# TUDSSL_condenar__Hardware_PCBs_Mainboard.net
KiCad netlist of a schematic drawn in Altium Designer
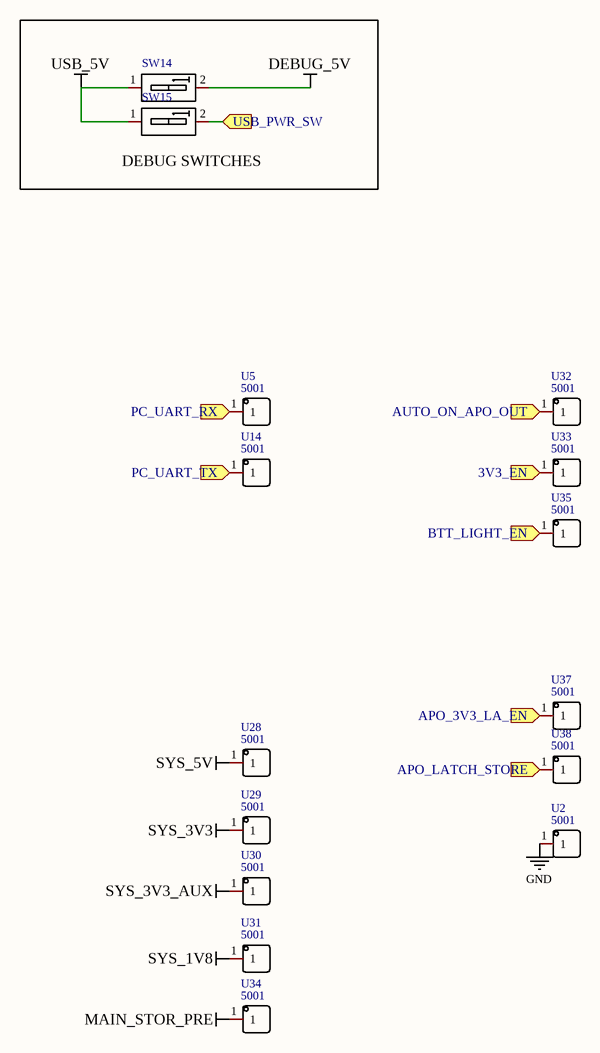
[diagram p0: TUDSSL_condenar__Hardware_PCBs_Mainboard_Board_TUD-V2-EnergyHarvestingConsole_TUD-EnergyHarvestingConsole_1__4_Debugging.schdoc]

(export (version "E")
  (design (tool "Eeschema 10.0.6"))
  (components
    (comp (ref "SW14")
      (value "DSIC01LSGET")
      (description "Type:平拨，凸起式 Circuit:SPST Number of Positions:1 Lead Pitch:2.54mm Color:Black")
      (fields (field (name "MANUFACTURER") "YE"))
      (libsource (lib "altium-import") (part "root_0_DSIC01LSGET_"))
    )
    (comp (ref "SW15")
      (value "DSIC01LSGET")
      (description "Type:平拨，凸起式 Circuit:SPST Number of Positions:1 Lead Pitch:2.54mm Color:Black")
      (fields (field (name "MANUFACTURER") "YE"))
      (libsource (lib "altium-import") (part "root_0_DSIC01LSGET_"))
    )
    (comp (ref "U2")
      (value "5001")
      (fields (field (name "NAME") "5001") (field (name "MANUFACTURER") "Keystone"))
      (libsource (lib "altium-import") (part "root_0_5001_"))
    )
    (comp (ref "U5")
      (value "5001")
      (fields (field (name "NAME") "5001") (field (name "MANUFACTURER") "Keystone"))
      (libsource (lib "altium-import") (part "root_0_5001_"))
    )
    (comp (ref "U14")
      (value "5001")
      (fields (field (name "NAME") "5001") (field (name "MANUFACTURER") "Keystone"))
      (libsource (lib "altium-import") (part "root_0_5001_"))
    )
    (comp (ref "U28")
      (value "5001")
      (fields (field (name "NAME") "5001") (field (name "MANUFACTURER") "Keystone"))
      (libsource (lib "altium-import") (part "root_0_5001_"))
    )
    (comp (ref "U29")
      (value "5001")
      (fields (field (name "NAME") "5001") (field (name "MANUFACTURER") "Keystone"))
      (libsource (lib "altium-import") (part "root_0_5001_"))
    )
    (comp (ref "U30")
      (value "5001")
      (fields (field (name "NAME") "5001") (field (name "MANUFACTURER") "Keystone"))
      (libsource (lib "altium-import") (part "root_0_5001_"))
    )
    (comp (ref "U31")
      (value "5001")
      (fields (field (name "NAME") "5001") (field (name "MANUFACTURER") "Keystone"))
      (libsource (lib "altium-import") (part "root_0_5001_"))
    )
    (comp (ref "U32")
      (value "5001")
      (fields (field (name "NAME") "5001") (field (name "MANUFACTURER") "Keystone"))
      (libsource (lib "altium-import") (part "root_0_5001_"))
    )
    (comp (ref "U33")
      (value "5001")
      (fields (field (name "NAME") "5001") (field (name "MANUFACTURER") "Keystone"))
      (libsource (lib "altium-import") (part "root_0_5001_"))
    )
    (comp (ref "U34")
      (value "5001")
      (fields (field (name "NAME") "5001") (field (name "MANUFACTURER") "Keystone"))
      (libsource (lib "altium-import") (part "root_0_5001_"))
    )
    (comp (ref "U35")
      (value "5001")
      (fields (field (name "NAME") "5001") (field (name "MANUFACTURER") "Keystone"))
      (libsource (lib "altium-import") (part "root_0_5001_"))
    )
    (comp (ref "U37")
      (value "5001")
      (fields (field (name "NAME") "5001") (field (name "MANUFACTURER") "Keystone"))
      (libsource (lib "altium-import") (part "root_0_5001_"))
    )
    (comp (ref "U38")
      (value "5001")
      (fields (field (name "NAME") "5001") (field (name "MANUFACTURER") "Keystone"))
      (libsource (lib "altium-import") (part "root_0_5001_"))
    )
  )
  (nets
    (net (code "1") (name "/3V3_EN") (class "Default")
      (node (ref "U33") (pin "1") (pinfunction "1_1") (pintype "passive"))
    )
    (net (code "2") (name "/APO_3V3_LA_EN") (class "Default")
      (node (ref "U37") (pin "1") (pinfunction "1_1") (pintype "passive"))
    )
    (net (code "3") (name "/APO_LATCH_STORE") (class "Default")
      (node (ref "U38") (pin "1") (pinfunction "1_1") (pintype "passive"))
    )
    (net (code "4") (name "/AUTO_ON_APO_OUT") (class "Default")
      (node (ref "U32") (pin "1") (pinfunction "1_1") (pintype "passive"))
    )
    (net (code "5") (name "/BTT_LIGHT_EN") (class "Default")
      (node (ref "U35") (pin "1") (pinfunction "1_1") (pintype "passive"))
    )
    (net (code "6") (name "/PC_UART_RX") (class "Default")
      (node (ref "U5") (pin "1") (pinfunction "1_1") (pintype "passive"))
    )
    (net (code "7") (name "/PC_UART_TX") (class "Default")
      (node (ref "U14") (pin "1") (pinfunction "1_1") (pintype "passive"))
    )
    (net (code "8") (name "/USB_PWR_SW") (class "Default")
      (node (ref "SW15") (pin "2") (pinfunction "A2_2") (pintype "passive"))
    )
    (net (code "9") (name "DEBUG_5V") (class "Default")
      (node (ref "SW14") (pin "2") (pinfunction "A2_2") (pintype "passive"))
    )
    (net (code "10") (name "GND") (class "Default")
      (node (ref "U2") (pin "1") (pinfunction "1_1") (pintype "passive"))
    )
    (net (code "11") (name "MAIN_STOR_PRE") (class "Default")
      (node (ref "U34") (pin "1") (pinfunction "1_1") (pintype "passive"))
    )
    (net (code "12") (name "SYS_1V8") (class "Default")
      (node (ref "U31") (pin "1") (pinfunction "1_1") (pintype "passive"))
    )
    (net (code "13") (name "SYS_3V3") (class "Default")
      (node (ref "U29") (pin "1") (pinfunction "1_1") (pintype "passive"))
    )
    (net (code "14") (name "SYS_3V3_AUX") (class "Default")
      (node (ref "U30") (pin "1") (pinfunction "1_1") (pintype "passive"))
    )
    (net (code "15") (name "SYS_5V") (class "Default")
      (node (ref "U28") (pin "1") (pinfunction "1_1") (pintype "passive"))
    )
    (net (code "16") (name "USB_5V") (class "Default")
      (node (ref "SW14") (pin "1") (pinfunction "A1_1") (pintype "passive"))
      (node (ref "SW15") (pin "1") (pinfunction "A1_1") (pintype "passive"))
    )
  )
)
